# Nestling_2_1_EXB_Interface.net
KiCad netlist of a schematic drawn in Altium Designer
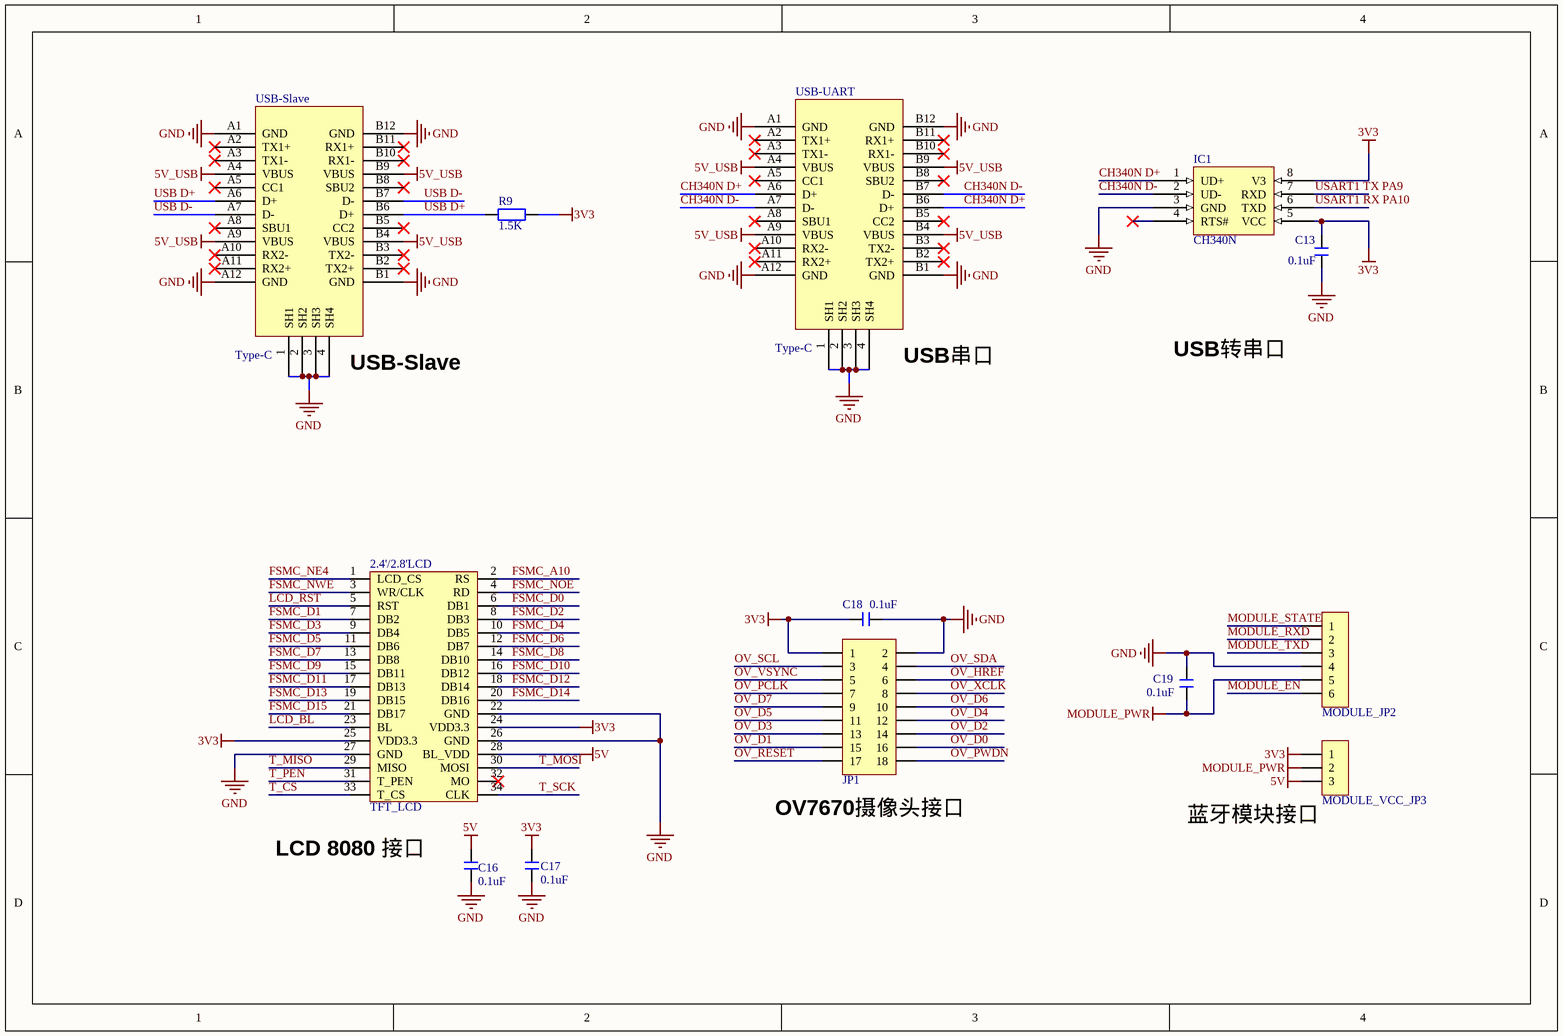
[diagram p0: Nestling_2.1_EXB_Interface.SchDoc]

(export (version "E")
  (design (tool "Eeschema 10.0.6"))
  (components
    (comp (ref "2.4'/2.8'LCD")
      (value "TFT_LCD")
      (footprint "db2*17-4.3")
      (libsource (lib "altium-import") (part "root_0_TFT_LCD_"))
    )
    (comp (ref "C13")
      (value "0.1uF")
      (footprint "C 0603_M")
      (description "无极性贴片电容")
      (fields (field (name "版权归属") "源创客"))
      (libsource (lib "altium-import") (part "root_1_C_"))
    )
    (comp (ref "C16")
      (value "0.1uF")
      (footprint "C 0603_M")
      (description "无极性贴片电容")
      (fields (field (name "版权归属") "源创客"))
      (libsource (lib "altium-import") (part "root_1_C_"))
    )
    (comp (ref "C17")
      (value "0.1uF")
      (footprint "C 0603_M")
      (description "无极性贴片电容")
      (fields (field (name "版权归属") "源创客"))
      (libsource (lib "altium-import") (part "root_3_C_"))
    )
    (comp (ref "C18")
      (value "0.1uF")
      (footprint "C 0603_M")
      (description "无极性贴片电容")
      (fields (field (name "版权归属") "源创客"))
      (libsource (lib "altium-import") (part "root_0_C_"))
    )
    (comp (ref "C19")
      (value "0.1uF")
      (footprint "C 0603_M")
      (description "无极性贴片电容")
      (fields (field (name "版权归属") "源创客"))
      (libsource (lib "altium-import") (part "root_1_C_"))
    )
    (comp (ref "IC1")
      (value "CH340N")
      (footprint "SOP8_N")
      (description "USB 转串口芯片 CH330/CH340N")
      (libsource (lib "altium-import") (part "root_0_CH340N_"))
    )
    (comp (ref "JP1")
      (value "Header 9X2")
      (footprint "HDR2.54-LI-2x9P")
      (description "9*2P接插件")
      (fields (field (name "版权归属") "源创客"))
      (libsource (lib "altium-import") (part "root_0_Header 9X2_"))
    )
    (comp (ref "MODULE_JP2")
      (value "HDR-1X6")
      (footprint "HDR2.54-M-LI-6P")
      (description "6P接插件")
      (fields (field (name "版权归属") "源创客"))
      (libsource (lib "altium-import") (part "root_0_Header 6_"))
    )
    (comp (ref "MODULE_VCC_JP3")
      (value "HDR-1X3")
      (footprint "HDR2.54-LI-3P")
      (description "3P接插件")
      (fields (field (name "版权归属") "源创客"))
      (libsource (lib "altium-import") (part "root_0_Header 3_"))
    )
    (comp (ref "R9")
      (value "1.5K")
      (footprint "R 0603_M")
      (description "Resistor")
      (libsource (lib "General") (part "RES"))
    )
    (comp (ref "USB-Slave")
      (value "Type-C")
      (footprint "Type-C")
      (libsource (lib "altium-import") (part "root_0_Type-C_"))
    )
    (comp (ref "USB-UART")
      (value "Type-C")
      (footprint "Type-C")
      (libsource (lib "altium-import") (part "root_0_Type-C_"))
    )
  )
  (nets
    (net (code "1") (name "/CH340N D+") (class "Default")
      (node (ref "IC1") (pin "1") (pinfunction "UD+_1") (pintype "input"))
      (node (ref "USB-UART") (pin "A6") (pinfunction "D+_A6") (pintype "passive"))
      (node (ref "USB-UART") (pin "B6") (pinfunction "D+_B6") (pintype "passive"))
    )
    (net (code "2") (name "/CH340N D-") (class "Default")
      (node (ref "IC1") (pin "2") (pinfunction "UD-_2") (pintype "input"))
      (node (ref "USB-UART") (pin "A7") (pinfunction "D-_A7") (pintype "passive"))
      (node (ref "USB-UART") (pin "B7") (pinfunction "D-_B7") (pintype "passive"))
    )
    (net (code "3") (name "/FSMC_A10") (class "Default")
      (node (ref "2.4'/2.8'LCD") (pin "2") (pinfunction "RS_2") (pintype "passive"))
    )
    (net (code "4") (name "/FSMC_D0") (class "Default")
      (node (ref "2.4'/2.8'LCD") (pin "6") (pinfunction "DB1_6") (pintype "passive"))
    )
    (net (code "5") (name "/FSMC_D1") (class "Default")
      (node (ref "2.4'/2.8'LCD") (pin "7") (pinfunction "DB2_7") (pintype "passive"))
    )
    (net (code "6") (name "/FSMC_D2") (class "Default")
      (node (ref "2.4'/2.8'LCD") (pin "8") (pinfunction "DB3_8") (pintype "passive"))
    )
    (net (code "7") (name "/FSMC_D3") (class "Default")
      (node (ref "2.4'/2.8'LCD") (pin "9") (pinfunction "DB4_9") (pintype "passive"))
    )
    (net (code "8") (name "/FSMC_D4") (class "Default")
      (node (ref "2.4'/2.8'LCD") (pin "10") (pinfunction "DB5_10") (pintype "passive"))
    )
    (net (code "9") (name "/FSMC_D5") (class "Default")
      (node (ref "2.4'/2.8'LCD") (pin "11") (pinfunction "DB6_11") (pintype "passive"))
    )
    (net (code "10") (name "/FSMC_D6") (class "Default")
      (node (ref "2.4'/2.8'LCD") (pin "12") (pinfunction "DB7_12") (pintype "passive"))
    )
    (net (code "11") (name "/FSMC_D7") (class "Default")
      (node (ref "2.4'/2.8'LCD") (pin "13") (pinfunction "DB8_13") (pintype "passive"))
    )
    (net (code "12") (name "/FSMC_D8") (class "Default")
      (node (ref "2.4'/2.8'LCD") (pin "14") (pinfunction "DB10_14") (pintype "passive"))
    )
    (net (code "13") (name "/FSMC_D9") (class "Default")
      (node (ref "2.4'/2.8'LCD") (pin "15") (pinfunction "DB11_15") (pintype "passive"))
    )
    (net (code "14") (name "/FSMC_D10") (class "Default")
      (node (ref "2.4'/2.8'LCD") (pin "16") (pinfunction "DB12_16") (pintype "passive"))
    )
    (net (code "15") (name "/FSMC_D11") (class "Default")
      (node (ref "2.4'/2.8'LCD") (pin "17") (pinfunction "DB13_17") (pintype "passive"))
    )
    (net (code "16") (name "/FSMC_D12") (class "Default")
      (node (ref "2.4'/2.8'LCD") (pin "18") (pinfunction "DB14_18") (pintype "passive"))
    )
    (net (code "17") (name "/FSMC_D13") (class "Default")
      (node (ref "2.4'/2.8'LCD") (pin "19") (pinfunction "DB15_19") (pintype "passive"))
    )
    (net (code "18") (name "/FSMC_D14") (class "Default")
      (node (ref "2.4'/2.8'LCD") (pin "20") (pinfunction "DB16_20") (pintype "passive"))
    )
    (net (code "19") (name "/FSMC_D15") (class "Default")
      (node (ref "2.4'/2.8'LCD") (pin "21") (pinfunction "DB17_21") (pintype "passive"))
    )
    (net (code "20") (name "/FSMC_NE4") (class "Default")
      (node (ref "2.4'/2.8'LCD") (pin "1") (pinfunction "LCD_CS_1") (pintype "passive"))
    )
    (net (code "21") (name "/FSMC_NOE") (class "Default")
      (node (ref "2.4'/2.8'LCD") (pin "4") (pinfunction "RD_4") (pintype "passive"))
    )
    (net (code "22") (name "/FSMC_NWE") (class "Default")
      (node (ref "2.4'/2.8'LCD") (pin "3") (pinfunction "WR/CLK_3") (pintype "passive"))
    )
    (net (code "23") (name "/LCD_BL") (class "Default")
      (node (ref "2.4'/2.8'LCD") (pin "23") (pinfunction "BL_23") (pintype "passive"))
    )
    (net (code "24") (name "/LCD_RST") (class "Default")
      (node (ref "2.4'/2.8'LCD") (pin "5") (pinfunction "RST_5") (pintype "passive"))
    )
    (net (code "25") (name "/MODULE_EN") (class "Default")
      (node (ref "MODULE_JP2") (pin "6") (pinfunction "6_6") (pintype "passive"))
    )
    (net (code "26") (name "/MODULE_RXD") (class "Default")
      (node (ref "MODULE_JP2") (pin "2") (pinfunction "2_2") (pintype "passive"))
    )
    (net (code "27") (name "/MODULE_STATE") (class "Default")
      (node (ref "MODULE_JP2") (pin "1") (pinfunction "1_1") (pintype "passive"))
    )
    (net (code "28") (name "/MODULE_TXD") (class "Default")
      (node (ref "MODULE_JP2") (pin "3") (pinfunction "3_3") (pintype "passive"))
    )
    (net (code "29") (name "/OV_D0") (class "Default")
      (node (ref "JP1") (pin "16") (pinfunction "16_16") (pintype "passive"))
    )
    (net (code "30") (name "/OV_D1") (class "Default")
      (node (ref "JP1") (pin "15") (pinfunction "15_15") (pintype "passive"))
    )
    (net (code "31") (name "/OV_D2") (class "Default")
      (node (ref "JP1") (pin "14") (pinfunction "14_14") (pintype "passive"))
    )
    (net (code "32") (name "/OV_D3") (class "Default")
      (node (ref "JP1") (pin "13") (pinfunction "13_13") (pintype "passive"))
    )
    (net (code "33") (name "/OV_D4") (class "Default")
      (node (ref "JP1") (pin "12") (pinfunction "12_12") (pintype "passive"))
    )
    (net (code "34") (name "/OV_D5") (class "Default")
      (node (ref "JP1") (pin "11") (pinfunction "11_11") (pintype "passive"))
    )
    (net (code "35") (name "/OV_D6") (class "Default")
      (node (ref "JP1") (pin "10") (pinfunction "10_10") (pintype "passive"))
    )
    (net (code "36") (name "/OV_D7") (class "Default")
      (node (ref "JP1") (pin "9") (pinfunction "9_9") (pintype "passive"))
    )
    (net (code "37") (name "/OV_HREF") (class "Default")
      (node (ref "JP1") (pin "6") (pinfunction "6_6") (pintype "passive"))
    )
    (net (code "38") (name "/OV_PCLK") (class "Default")
      (node (ref "JP1") (pin "7") (pinfunction "7_7") (pintype "passive"))
    )
    (net (code "39") (name "/OV_PWDN") (class "Default")
      (node (ref "JP1") (pin "18") (pinfunction "18_18") (pintype "passive"))
    )
    (net (code "40") (name "/OV_RESET") (class "Default")
      (node (ref "JP1") (pin "17") (pinfunction "17_17") (pintype "passive"))
    )
    (net (code "41") (name "/OV_SCL") (class "Default")
      (node (ref "JP1") (pin "3") (pinfunction "3_3") (pintype "passive"))
    )
    (net (code "42") (name "/OV_SDA") (class "Default")
      (node (ref "JP1") (pin "4") (pinfunction "4_4") (pintype "passive"))
    )
    (net (code "43") (name "/OV_VSYNC") (class "Default")
      (node (ref "JP1") (pin "5") (pinfunction "5_5") (pintype "passive"))
    )
    (net (code "44") (name "/OV_XCLK") (class "Default")
      (node (ref "JP1") (pin "8") (pinfunction "8_8") (pintype "passive"))
    )
    (net (code "45") (name "/T_CS") (class "Default")
      (node (ref "2.4'/2.8'LCD") (pin "33") (pinfunction "T_CS_33") (pintype "passive"))
    )
    (net (code "46") (name "/T_MISO") (class "Default")
      (node (ref "2.4'/2.8'LCD") (pin "29") (pinfunction "MISO_29") (pintype "passive"))
    )
    (net (code "47") (name "/T_MOSI") (class "Default")
      (node (ref "2.4'/2.8'LCD") (pin "30") (pinfunction "MOSI_30") (pintype "passive"))
    )
    (net (code "48") (name "/T_PEN") (class "Default")
      (node (ref "2.4'/2.8'LCD") (pin "31") (pinfunction "T_PEN_31") (pintype "passive"))
    )
    (net (code "49") (name "/T_SCK") (class "Default")
      (node (ref "2.4'/2.8'LCD") (pin "34") (pinfunction "CLK_34") (pintype "passive"))
    )
    (net (code "50") (name "/USART1 RX PA10") (class "Default")
      (node (ref "IC1") (pin "6") (pinfunction "TXD_6") (pintype "input"))
    )
    (net (code "51") (name "/USART1 TX PA9") (class "Default")
      (node (ref "IC1") (pin "7") (pinfunction "RXD_7") (pintype "input"))
    )
    (net (code "52") (name "/USB D+") (class "Default")
      (node (ref "R9") (pin "2") (pinfunction "2_2") (pintype "passive"))
      (node (ref "USB-Slave") (pin "A6") (pinfunction "D+_A6") (pintype "passive"))
      (node (ref "USB-Slave") (pin "B6") (pinfunction "D+_B6") (pintype "passive"))
    )
    (net (code "53") (name "/USB D-") (class "Default")
      (node (ref "USB-Slave") (pin "A7") (pinfunction "D-_A7") (pintype "passive"))
      (node (ref "USB-Slave") (pin "B7") (pinfunction "D-_B7") (pintype "passive"))
    )
    (net (code "54") (name "3V3") (class "Default")
      (node (ref "2.4'/2.8'LCD") (pin "24") (pinfunction "VDD3.3_24") (pintype "passive"))
      (node (ref "2.4'/2.8'LCD") (pin "25") (pinfunction "VDD3.3_25") (pintype "passive"))
      (node (ref "C13") (pin "2") (pinfunction "2_2") (pintype "passive"))
      (node (ref "C17") (pin "1") (pinfunction "1_1") (pintype "passive"))
      (node (ref "C18") (pin "1") (pinfunction "1_1") (pintype "passive"))
      (node (ref "IC1") (pin "5") (pinfunction "VCC_5") (pintype "input"))
      (node (ref "IC1") (pin "8") (pinfunction "V3_8") (pintype "input"))
      (node (ref "JP1") (pin "1") (pinfunction "1_1") (pintype "passive"))
      (node (ref "MODULE_VCC_JP3") (pin "1") (pinfunction "1_1") (pintype "passive"))
      (node (ref "R9") (pin "1") (pinfunction "1_1") (pintype "passive"))
    )
    (net (code "55") (name "5V") (class "Default")
      (node (ref "2.4'/2.8'LCD") (pin "28") (pinfunction "BL_VDD_28") (pintype "passive"))
      (node (ref "C16") (pin "2") (pinfunction "2_2") (pintype "passive"))
      (node (ref "MODULE_VCC_JP3") (pin "3") (pinfunction "3_3") (pintype "passive"))
    )
    (net (code "56") (name "5V_USB") (class "Default")
      (node (ref "USB-Slave") (pin "A4") (pinfunction "VBUS_A4") (pintype "passive"))
      (node (ref "USB-Slave") (pin "A9") (pinfunction "VBUS_A9") (pintype "passive"))
      (node (ref "USB-Slave") (pin "B4") (pinfunction "VBUS_B4") (pintype "passive"))
      (node (ref "USB-Slave") (pin "B9") (pinfunction "VBUS_B9") (pintype "passive"))
      (node (ref "USB-UART") (pin "A4") (pinfunction "VBUS_A4") (pintype "passive"))
      (node (ref "USB-UART") (pin "A9") (pinfunction "VBUS_A9") (pintype "passive"))
      (node (ref "USB-UART") (pin "B4") (pinfunction "VBUS_B4") (pintype "passive"))
      (node (ref "USB-UART") (pin "B9") (pinfunction "VBUS_B9") (pintype "passive"))
    )
    (net (code "57") (name "GND") (class "Default")
      (node (ref "2.4'/2.8'LCD") (pin "22") (pinfunction "GND_22") (pintype "passive"))
      (node (ref "2.4'/2.8'LCD") (pin "26") (pinfunction "GND_26") (pintype "passive"))
      (node (ref "2.4'/2.8'LCD") (pin "27") (pinfunction "GND_27") (pintype "passive"))
      (node (ref "C13") (pin "1") (pinfunction "1_1") (pintype "passive"))
      (node (ref "C16") (pin "1") (pinfunction "1_1") (pintype "passive"))
      (node (ref "C17") (pin "2") (pinfunction "2_2") (pintype "passive"))
      (node (ref "C18") (pin "2") (pinfunction "2_2") (pintype "passive"))
      (node (ref "C19") (pin "2") (pinfunction "2_2") (pintype "passive"))
      (node (ref "IC1") (pin "3") (pinfunction "GND_3") (pintype "input"))
      (node (ref "JP1") (pin "2") (pinfunction "2_2") (pintype "passive"))
      (node (ref "MODULE_JP2") (pin "4") (pinfunction "4_4") (pintype "passive"))
      (node (ref "USB-Slave") (pin "1") (pinfunction "SH1_1") (pintype "passive"))
      (node (ref "USB-Slave") (pin "2") (pinfunction "SH2_2") (pintype "passive"))
      (node (ref "USB-Slave") (pin "3") (pinfunction "SH3_3") (pintype "passive"))
      (node (ref "USB-Slave") (pin "4") (pinfunction "SH4_4") (pintype "passive"))
      (node (ref "USB-Slave") (pin "A1") (pinfunction "GND_A1") (pintype "passive"))
      (node (ref "USB-Slave") (pin "A12") (pinfunction "GND_A12") (pintype "passive"))
      (node (ref "USB-Slave") (pin "B1") (pinfunction "GND_B1") (pintype "passive"))
      (node (ref "USB-Slave") (pin "B12") (pinfunction "GND_B12") (pintype "passive"))
      (node (ref "USB-UART") (pin "1") (pinfunction "SH1_1") (pintype "passive"))
      (node (ref "USB-UART") (pin "2") (pinfunction "SH2_2") (pintype "passive"))
      (node (ref "USB-UART") (pin "3") (pinfunction "SH3_3") (pintype "passive"))
      (node (ref "USB-UART") (pin "4") (pinfunction "SH4_4") (pintype "passive"))
      (node (ref "USB-UART") (pin "A1") (pinfunction "GND_A1") (pintype "passive"))
      (node (ref "USB-UART") (pin "A12") (pinfunction "GND_A12") (pintype "passive"))
      (node (ref "USB-UART") (pin "B1") (pinfunction "GND_B1") (pintype "passive"))
      (node (ref "USB-UART") (pin "B12") (pinfunction "GND_B12") (pintype "passive"))
    )
    (net (code "58") (name "MODULE_PWR") (class "Default")
      (node (ref "C19") (pin "1") (pinfunction "1_1") (pintype "passive"))
      (node (ref "MODULE_JP2") (pin "5") (pinfunction "5_5") (pintype "passive"))
      (node (ref "MODULE_VCC_JP3") (pin "2") (pinfunction "2_2") (pintype "passive"))
    )
    (net (code "59") (name "unconnected-(2.4'/2.8'LCD-MO-Pad32)") (class "Default")
      (node (ref "2.4'/2.8'LCD") (pin "32") (pinfunction "MO_32") (pintype "passive+no_connect"))
    )
    (net (code "60") (name "unconnected-(IC1-RTS#-Pad4)") (class "Default")
      (node (ref "IC1") (pin "4") (pinfunction "RTS#_4") (pintype "input+no_connect"))
    )
    (net (code "61") (name "unconnected-(USB-Slave-CC1-PadA5)") (class "Default")
      (node (ref "USB-Slave") (pin "A5") (pinfunction "CC1_A5") (pintype "passive+no_connect"))
    )
    (net (code "62") (name "unconnected-(USB-Slave-CC2-PadB5)") (class "Default")
      (node (ref "USB-Slave") (pin "B5") (pinfunction "CC2_B5") (pintype "passive+no_connect"))
    )
    (net (code "63") (name "unconnected-(USB-Slave-RX1+-PadB11)") (class "Default")
      (node (ref "USB-Slave") (pin "B11") (pinfunction "RX1+_B11") (pintype "passive+no_connect"))
    )
    (net (code "64") (name "unconnected-(USB-Slave-RX1--PadB10)") (class "Default")
      (node (ref "USB-Slave") (pin "B10") (pinfunction "RX1-_B10") (pintype "passive+no_connect"))
    )
    (net (code "65") (name "unconnected-(USB-Slave-RX2+-PadA11)") (class "Default")
      (node (ref "USB-Slave") (pin "A11") (pinfunction "RX2+_A11") (pintype "passive+no_connect"))
    )
    (net (code "66") (name "unconnected-(USB-Slave-RX2--PadA10)") (class "Default")
      (node (ref "USB-Slave") (pin "A10") (pinfunction "RX2-_A10") (pintype "passive+no_connect"))
    )
    (net (code "67") (name "unconnected-(USB-Slave-SBU1-PadA8)") (class "Default")
      (node (ref "USB-Slave") (pin "A8") (pinfunction "SBU1_A8") (pintype "passive+no_connect"))
    )
    (net (code "68") (name "unconnected-(USB-Slave-SBU2-PadB8)") (class "Default")
      (node (ref "USB-Slave") (pin "B8") (pinfunction "SBU2_B8") (pintype "passive+no_connect"))
    )
    (net (code "69") (name "unconnected-(USB-Slave-TX1+-PadA2)") (class "Default")
      (node (ref "USB-Slave") (pin "A2") (pinfunction "TX1+_A2") (pintype "passive+no_connect"))
    )
    (net (code "70") (name "unconnected-(USB-Slave-TX1--PadA3)") (class "Default")
      (node (ref "USB-Slave") (pin "A3") (pinfunction "TX1-_A3") (pintype "passive+no_connect"))
    )
    (net (code "71") (name "unconnected-(USB-Slave-TX2+-PadB2)") (class "Default")
      (node (ref "USB-Slave") (pin "B2") (pinfunction "TX2+_B2") (pintype "passive+no_connect"))
    )
    (net (code "72") (name "unconnected-(USB-Slave-TX2--PadB3)") (class "Default")
      (node (ref "USB-Slave") (pin "B3") (pinfunction "TX2-_B3") (pintype "passive+no_connect"))
    )
    (net (code "73") (name "unconnected-(USB-UART-CC1-PadA5)") (class "Default")
      (node (ref "USB-UART") (pin "A5") (pinfunction "CC1_A5") (pintype "passive+no_connect"))
    )
    (net (code "74") (name "unconnected-(USB-UART-CC2-PadB5)") (class "Default")
      (node (ref "USB-UART") (pin "B5") (pinfunction "CC2_B5") (pintype "passive+no_connect"))
    )
    (net (code "75") (name "unconnected-(USB-UART-RX1+-PadB11)") (class "Default")
      (node (ref "USB-UART") (pin "B11") (pinfunction "RX1+_B11") (pintype "passive+no_connect"))
    )
    (net (code "76") (name "unconnected-(USB-UART-RX1--PadB10)") (class "Default")
      (node (ref "USB-UART") (pin "B10") (pinfunction "RX1-_B10") (pintype "passive+no_connect"))
    )
    (net (code "77") (name "unconnected-(USB-UART-RX2+-PadA11)") (class "Default")
      (node (ref "USB-UART") (pin "A11") (pinfunction "RX2+_A11") (pintype "passive+no_connect"))
    )
    (net (code "78") (name "unconnected-(USB-UART-RX2--PadA10)") (class "Default")
      (node (ref "USB-UART") (pin "A10") (pinfunction "RX2-_A10") (pintype "passive+no_connect"))
    )
    (net (code "79") (name "unconnected-(USB-UART-SBU1-PadA8)") (class "Default")
      (node (ref "USB-UART") (pin "A8") (pinfunction "SBU1_A8") (pintype "passive+no_connect"))
    )
    (net (code "80") (name "unconnected-(USB-UART-SBU2-PadB8)") (class "Default")
      (node (ref "USB-UART") (pin "B8") (pinfunction "SBU2_B8") (pintype "passive+no_connect"))
    )
    (net (code "81") (name "unconnected-(USB-UART-TX1+-PadA2)") (class "Default")
      (node (ref "USB-UART") (pin "A2") (pinfunction "TX1+_A2") (pintype "passive+no_connect"))
    )
    (net (code "82") (name "unconnected-(USB-UART-TX1--PadA3)") (class "Default")
      (node (ref "USB-UART") (pin "A3") (pinfunction "TX1-_A3") (pintype "passive+no_connect"))
    )
    (net (code "83") (name "unconnected-(USB-UART-TX2+-PadB2)") (class "Default")
      (node (ref "USB-UART") (pin "B2") (pinfunction "TX2+_B2") (pintype "passive+no_connect"))
    )
    (net (code "84") (name "unconnected-(USB-UART-TX2--PadB3)") (class "Default")
      (node (ref "USB-UART") (pin "B3") (pinfunction "TX2-_B3") (pintype "passive+no_connect"))
    )
  )
)
